# untitledv1_0.net
KiCad netlist of a schematic drawn in EAGLE
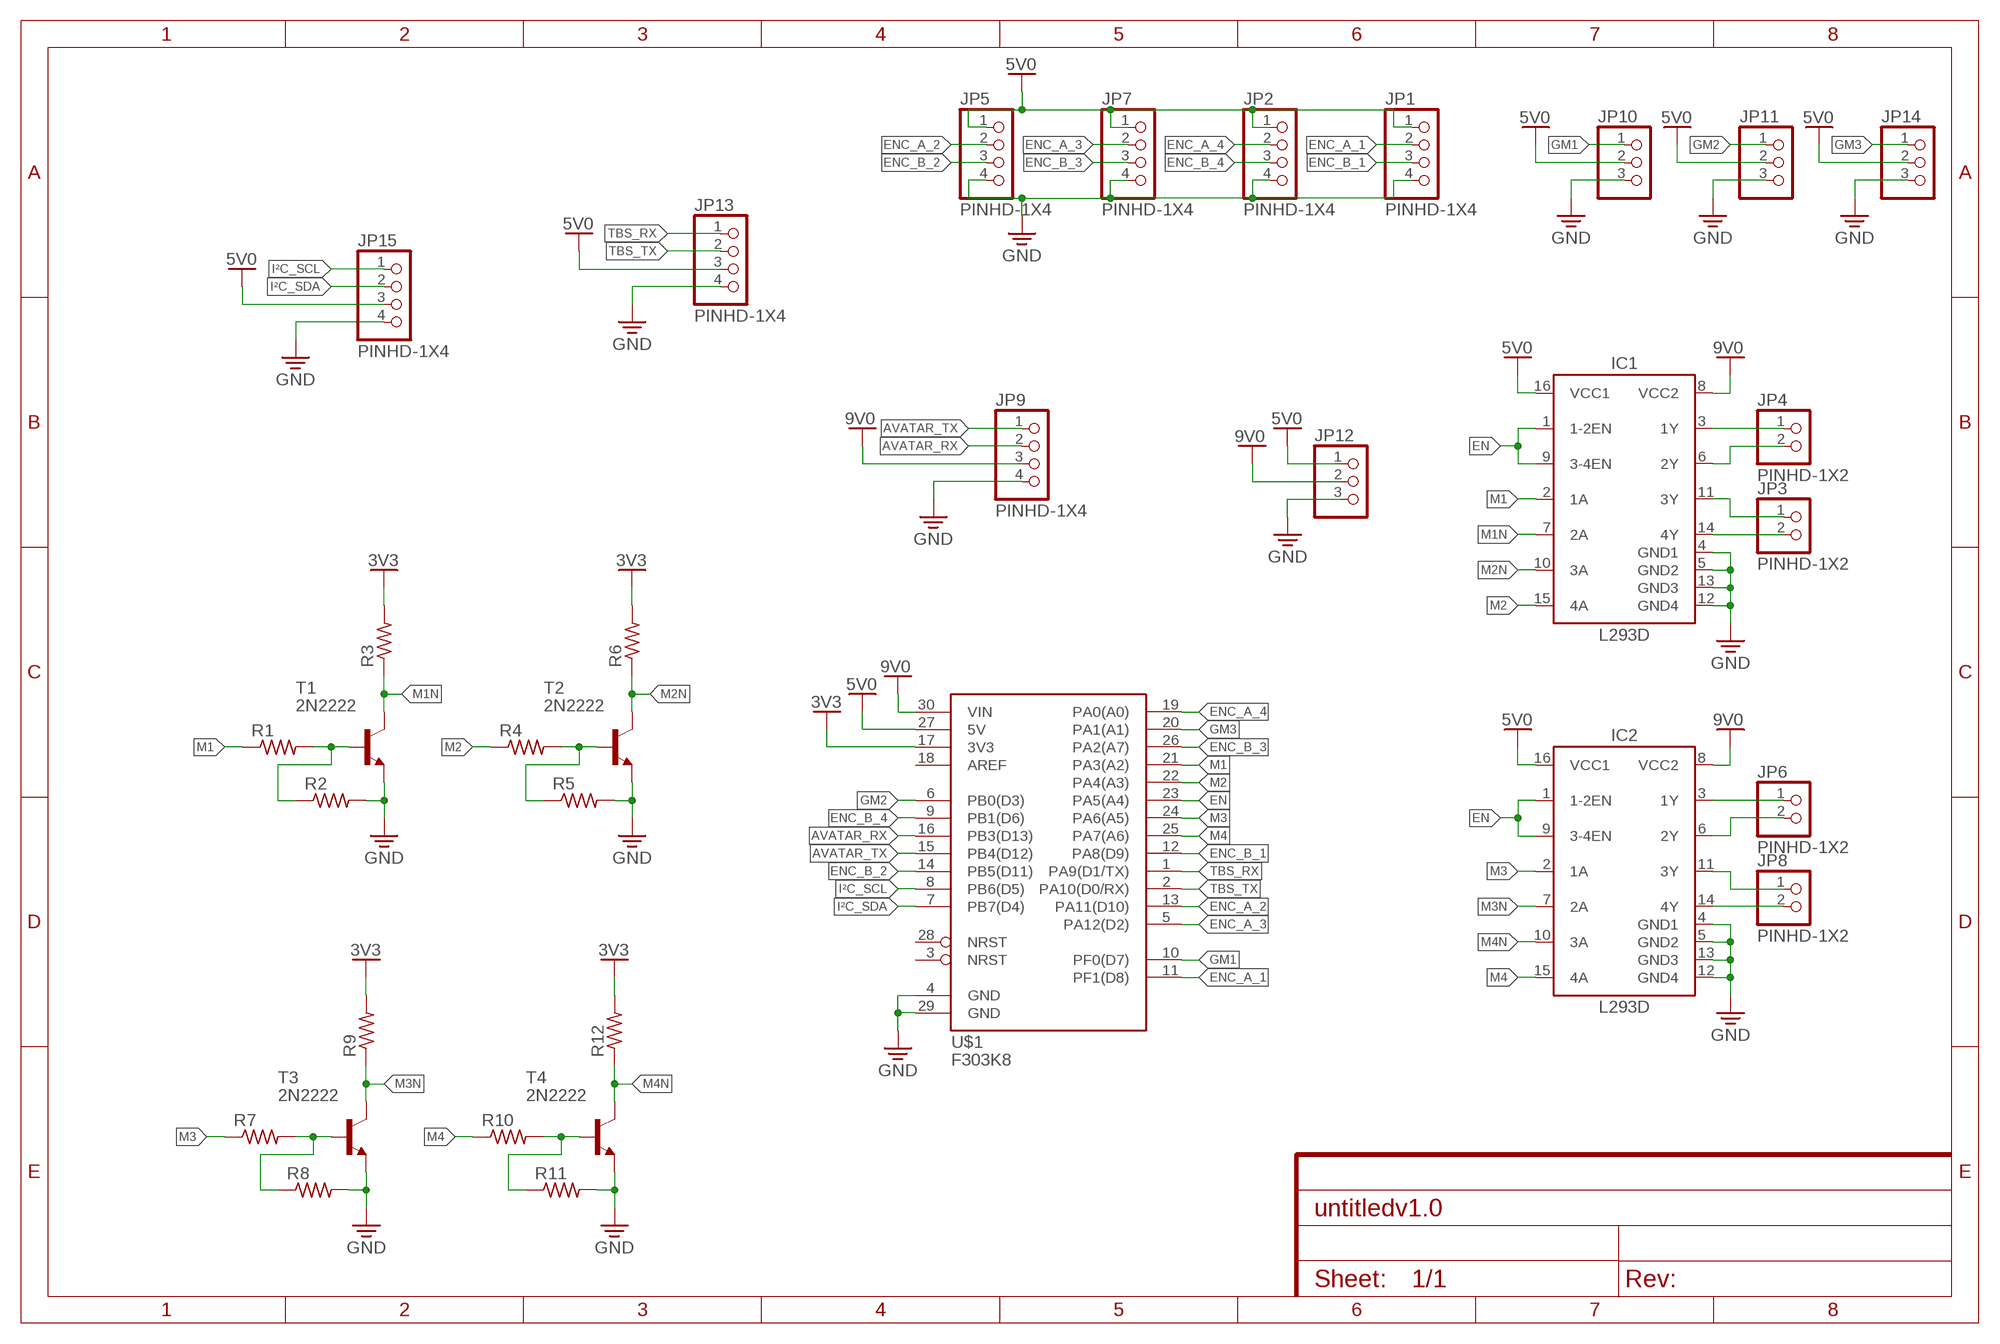
[diagram p0: schematic, sheet 1]

(export (version "E")
  (design (tool "Eeschema 10.0.6"))
  (components
    (comp (ref "IC1")
      (value "L293D")
      (footprint "eagle-import:DIP762W53P254L1969H508Q16B")
      (fields (field (name "MANUFACTURER") "STMicroelectronics"))
      (libsource (lib "eagle-import") (part "L293D"))
    )
    (comp (ref "IC2")
      (value "L293D")
      (footprint "eagle-import:DIP762W53P254L1969H508Q16B")
      (fields (field (name "MANUFACTURER") "STMicroelectronics"))
      (libsource (lib "eagle-import") (part "L293D"))
    )
    (comp (ref "JP1")
      (value "PINHD-1X4")
      (footprint "eagle-import:1X04")
      (libsource (lib "eagle-import") (part "PINHD-1X4"))
    )
    (comp (ref "JP2")
      (value "PINHD-1X4")
      (footprint "eagle-import:1X04")
      (libsource (lib "eagle-import") (part "PINHD-1X4"))
    )
    (comp (ref "JP3")
      (value "PINHD-1X2")
      (footprint "eagle-import:1X02")
      (libsource (lib "eagle-import") (part "PINHD-1X2"))
    )
    (comp (ref "JP4")
      (value "PINHD-1X2")
      (footprint "eagle-import:1X02")
      (libsource (lib "eagle-import") (part "PINHD-1X2"))
    )
    (comp (ref "JP5")
      (value "PINHD-1X4")
      (footprint "eagle-import:1X04")
      (libsource (lib "eagle-import") (part "PINHD-1X4"))
    )
    (comp (ref "JP6")
      (value "PINHD-1X2")
      (footprint "eagle-import:1X02")
      (libsource (lib "eagle-import") (part "PINHD-1X2"))
    )
    (comp (ref "JP7")
      (value "PINHD-1X4")
      (footprint "eagle-import:1X04")
      (libsource (lib "eagle-import") (part "PINHD-1X4"))
    )
    (comp (ref "JP8")
      (value "PINHD-1X2")
      (footprint "eagle-import:1X02")
      (libsource (lib "eagle-import") (part "PINHD-1X2"))
    )
    (comp (ref "JP9")
      (value "PINHD-1X4")
      (footprint "eagle-import:1X04")
      (libsource (lib "eagle-import") (part "PINHD-1X4"))
    )
    (comp (ref "JP10")
      (value "PINHD-1X3")
      (footprint "eagle-import:1X03")
      (libsource (lib "eagle-import") (part "PINHD-1X3"))
    )
    (comp (ref "JP11")
      (value "PINHD-1X3")
      (footprint "eagle-import:1X03")
      (libsource (lib "eagle-import") (part "PINHD-1X3"))
    )
    (comp (ref "JP12")
      (value "PINHD-1X3")
      (footprint "eagle-import:1X03")
      (libsource (lib "eagle-import") (part "PINHD-1X3"))
    )
    (comp (ref "JP13")
      (value "PINHD-1X4")
      (footprint "eagle-import:1X04")
      (libsource (lib "eagle-import") (part "PINHD-1X4"))
    )
    (comp (ref "JP14")
      (value "PINHD-1X3")
      (footprint "eagle-import:1X03")
      (libsource (lib "eagle-import") (part "PINHD-1X3"))
    )
    (comp (ref "JP15")
      (value "PINHD-1X4")
      (footprint "eagle-import:1X04")
      (libsource (lib "eagle-import") (part "PINHD-1X4"))
    )
    (comp (ref "R1")
      (value "R-US_0204/2V")
      (footprint "eagle-import:0204V")
      (libsource (lib "eagle-import") (part "R-US_0204/2V"))
    )
    (comp (ref "R2")
      (value "R-US_0204/2V")
      (footprint "eagle-import:0204V")
      (libsource (lib "eagle-import") (part "R-US_0204/2V"))
    )
    (comp (ref "R3")
      (value "R-US_0204/2V")
      (footprint "eagle-import:0204V")
      (libsource (lib "eagle-import") (part "R-US_0204/2V"))
    )
    (comp (ref "R4")
      (value "R-US_0204/2V")
      (footprint "eagle-import:0204V")
      (libsource (lib "eagle-import") (part "R-US_0204/2V"))
    )
    (comp (ref "R5")
      (value "R-US_0204/2V")
      (footprint "eagle-import:0204V")
      (libsource (lib "eagle-import") (part "R-US_0204/2V"))
    )
    (comp (ref "R6")
      (value "R-US_0204/2V")
      (footprint "eagle-import:0204V")
      (libsource (lib "eagle-import") (part "R-US_0204/2V"))
    )
    (comp (ref "R7")
      (value "R-US_0204/2V")
      (footprint "eagle-import:0204V")
      (libsource (lib "eagle-import") (part "R-US_0204/2V"))
    )
    (comp (ref "R8")
      (value "R-US_0204/2V")
      (footprint "eagle-import:0204V")
      (libsource (lib "eagle-import") (part "R-US_0204/2V"))
    )
    (comp (ref "R9")
      (value "R-US_0204/2V")
      (footprint "eagle-import:0204V")
      (libsource (lib "eagle-import") (part "R-US_0204/2V"))
    )
    (comp (ref "R10")
      (value "R-US_0204/2V")
      (footprint "eagle-import:0204V")
      (libsource (lib "eagle-import") (part "R-US_0204/2V"))
    )
    (comp (ref "R11")
      (value "R-US_0204/2V")
      (footprint "eagle-import:0204V")
      (libsource (lib "eagle-import") (part "R-US_0204/2V"))
    )
    (comp (ref "R12")
      (value "R-US_0204/2V")
      (footprint "eagle-import:0204V")
      (libsource (lib "eagle-import") (part "R-US_0204/2V"))
    )
    (comp (ref "T1")
      (value "2N2222")
      (footprint "eagle-import:TO92-EBC-OVAL")
      (libsource (lib "eagle-import") (part "2N2222"))
    )
    (comp (ref "T2")
      (value "2N2222")
      (footprint "eagle-import:TO92-EBC-OVAL")
      (libsource (lib "eagle-import") (part "2N2222"))
    )
    (comp (ref "T3")
      (value "2N2222")
      (footprint "eagle-import:TO92-EBC-OVAL")
      (libsource (lib "eagle-import") (part "2N2222"))
    )
    (comp (ref "T4")
      (value "2N2222")
      (footprint "eagle-import:TO92-EBC-OVAL")
      (libsource (lib "eagle-import") (part "2N2222"))
    )
    (comp (ref "U$1")
      (value "F303K8")
      (footprint "eagle-import:NUCLEO_F303K8-V2")
      (libsource (lib "eagle-import") (part "F303K8"))
    )
  )
  (nets
    (net (code "1") (name "3V3") (class "Default")
      (node (ref "R12") (pin "2") (pinfunction "2_2") (pintype "passive"))
      (node (ref "R3") (pin "2") (pinfunction "2_2") (pintype "passive"))
      (node (ref "R6") (pin "2") (pinfunction "2_2") (pintype "passive"))
      (node (ref "R9") (pin "2") (pinfunction "2_2") (pintype "passive"))
      (node (ref "U$1") (pin "17") (pinfunction "3V3_17") (pintype "output"))
    )
    (net (code "2") (name "5V0") (class "Default")
      (node (ref "IC1") (pin "16") (pinfunction "VCC1_16") (pintype "passive"))
      (node (ref "IC2") (pin "16") (pinfunction "VCC1_16") (pintype "passive"))
      (node (ref "JP1") (pin "1") (pinfunction "1_1") (pintype "passive"))
      (node (ref "JP10") (pin "2") (pinfunction "2_2") (pintype "passive"))
      (node (ref "JP11") (pin "2") (pinfunction "2_2") (pintype "passive"))
      (node (ref "JP12") (pin "1") (pinfunction "1_1") (pintype "passive"))
      (node (ref "JP13") (pin "3") (pinfunction "3_3") (pintype "passive"))
      (node (ref "JP14") (pin "2") (pinfunction "2_2") (pintype "passive"))
      (node (ref "JP15") (pin "3") (pinfunction "3_3") (pintype "passive"))
      (node (ref "JP2") (pin "1") (pinfunction "1_1") (pintype "passive"))
      (node (ref "JP5") (pin "1") (pinfunction "1_1") (pintype "passive"))
      (node (ref "JP7") (pin "1") (pinfunction "1_1") (pintype "passive"))
      (node (ref "U$1") (pin "27") (pinfunction "5V_27") (pintype "power_in"))
    )
    (net (code "3") (name "9V0") (class "Default")
      (node (ref "IC1") (pin "8") (pinfunction "VCC2_8") (pintype "passive"))
      (node (ref "IC2") (pin "8") (pinfunction "VCC2_8") (pintype "passive"))
      (node (ref "JP12") (pin "2") (pinfunction "2_2") (pintype "passive"))
      (node (ref "JP9") (pin "3") (pinfunction "3_3") (pintype "passive"))
      (node (ref "U$1") (pin "30") (pinfunction "VIN_30") (pintype "power_in"))
    )
    (net (code "4") (name "AVATAR_RX") (class "Default")
      (node (ref "JP9") (pin "2") (pinfunction "2_2") (pintype "passive"))
      (node (ref "U$1") (pin "16") (pinfunction "PB3(D13)_16") (pintype "bidirectional"))
    )
    (net (code "5") (name "AVATAR_TX") (class "Default")
      (node (ref "JP9") (pin "1") (pinfunction "1_1") (pintype "passive"))
      (node (ref "U$1") (pin "15") (pinfunction "PB4(D12)_15") (pintype "bidirectional"))
    )
    (net (code "6") (name "EN") (class "Default")
      (node (ref "IC1") (pin "1") (pinfunction "1-2EN_1") (pintype "input"))
      (node (ref "IC1") (pin "9") (pinfunction "3-4EN_9") (pintype "input"))
      (node (ref "IC2") (pin "1") (pinfunction "1-2EN_1") (pintype "input"))
      (node (ref "IC2") (pin "9") (pinfunction "3-4EN_9") (pintype "input"))
      (node (ref "U$1") (pin "23") (pinfunction "PA5(A4)_23") (pintype "bidirectional"))
    )
    (net (code "7") (name "ENC_A_1") (class "Default")
      (node (ref "JP1") (pin "2") (pinfunction "2_2") (pintype "passive"))
      (node (ref "U$1") (pin "11") (pinfunction "PF1(D8)_11") (pintype "bidirectional"))
    )
    (net (code "8") (name "ENC_A_2") (class "Default")
      (node (ref "JP5") (pin "2") (pinfunction "2_2") (pintype "passive"))
      (node (ref "U$1") (pin "13") (pinfunction "PA11(D10)_13") (pintype "bidirectional"))
    )
    (net (code "9") (name "ENC_A_3") (class "Default")
      (node (ref "JP7") (pin "2") (pinfunction "2_2") (pintype "passive"))
      (node (ref "U$1") (pin "5") (pinfunction "PA12(D2)_5") (pintype "bidirectional"))
    )
    (net (code "10") (name "ENC_A_4") (class "Default")
      (node (ref "JP2") (pin "2") (pinfunction "2_2") (pintype "passive"))
      (node (ref "U$1") (pin "19") (pinfunction "PA0(A0)_19") (pintype "bidirectional"))
    )
    (net (code "11") (name "ENC_B_1") (class "Default")
      (node (ref "JP1") (pin "3") (pinfunction "3_3") (pintype "passive"))
      (node (ref "U$1") (pin "12") (pinfunction "PA8(D9)_12") (pintype "bidirectional"))
    )
    (net (code "12") (name "ENC_B_2") (class "Default")
      (node (ref "JP5") (pin "3") (pinfunction "3_3") (pintype "passive"))
      (node (ref "U$1") (pin "14") (pinfunction "PB5(D11)_14") (pintype "bidirectional"))
    )
    (net (code "13") (name "ENC_B_3") (class "Default")
      (node (ref "JP7") (pin "3") (pinfunction "3_3") (pintype "passive"))
      (node (ref "U$1") (pin "26") (pinfunction "PA2(A7)_26") (pintype "bidirectional"))
    )
    (net (code "14") (name "ENC_B_4") (class "Default")
      (node (ref "JP2") (pin "3") (pinfunction "3_3") (pintype "passive"))
      (node (ref "U$1") (pin "9") (pinfunction "PB1(D6)_9") (pintype "bidirectional"))
    )
    (net (code "15") (name "GM1") (class "Default")
      (node (ref "JP10") (pin "1") (pinfunction "1_1") (pintype "passive"))
      (node (ref "U$1") (pin "10") (pinfunction "PF0(D7)_10") (pintype "bidirectional"))
    )
    (net (code "16") (name "GM2") (class "Default")
      (node (ref "JP11") (pin "1") (pinfunction "1_1") (pintype "passive"))
      (node (ref "U$1") (pin "6") (pinfunction "PB0(D3)_6") (pintype "bidirectional"))
    )
    (net (code "17") (name "GM3") (class "Default")
      (node (ref "JP14") (pin "1") (pinfunction "1_1") (pintype "passive"))
      (node (ref "U$1") (pin "20") (pinfunction "PA1(A1)_20") (pintype "bidirectional"))
    )
    (net (code "18") (name "GND") (class "Default")
      (node (ref "IC1") (pin "12") (pinfunction "GND4_12") (pintype "passive"))
      (node (ref "IC1") (pin "13") (pinfunction "GND3_13") (pintype "passive"))
      (node (ref "IC1") (pin "4") (pinfunction "GND1_4") (pintype "passive"))
      (node (ref "IC1") (pin "5") (pinfunction "GND2_5") (pintype "passive"))
      (node (ref "IC2") (pin "12") (pinfunction "GND4_12") (pintype "passive"))
      (node (ref "IC2") (pin "13") (pinfunction "GND3_13") (pintype "passive"))
      (node (ref "IC2") (pin "4") (pinfunction "GND1_4") (pintype "passive"))
      (node (ref "IC2") (pin "5") (pinfunction "GND2_5") (pintype "passive"))
      (node (ref "JP1") (pin "4") (pinfunction "4_4") (pintype "passive"))
      (node (ref "JP10") (pin "3") (pinfunction "3_3") (pintype "passive"))
      (node (ref "JP11") (pin "3") (pinfunction "3_3") (pintype "passive"))
      (node (ref "JP12") (pin "3") (pinfunction "3_3") (pintype "passive"))
      (node (ref "JP13") (pin "4") (pinfunction "4_4") (pintype "passive"))
      (node (ref "JP14") (pin "3") (pinfunction "3_3") (pintype "passive"))
      (node (ref "JP15") (pin "4") (pinfunction "4_4") (pintype "passive"))
      (node (ref "JP2") (pin "4") (pinfunction "4_4") (pintype "passive"))
      (node (ref "JP5") (pin "4") (pinfunction "4_4") (pintype "passive"))
      (node (ref "JP7") (pin "4") (pinfunction "4_4") (pintype "passive"))
      (node (ref "JP9") (pin "4") (pinfunction "4_4") (pintype "passive"))
      (node (ref "R11") (pin "2") (pinfunction "2_2") (pintype "passive"))
      (node (ref "R2") (pin "2") (pinfunction "2_2") (pintype "passive"))
      (node (ref "R5") (pin "2") (pinfunction "2_2") (pintype "passive"))
      (node (ref "R8") (pin "2") (pinfunction "2_2") (pintype "passive"))
      (node (ref "T1") (pin "E") (pinfunction "E_E") (pintype "passive"))
      (node (ref "T2") (pin "E") (pinfunction "E_E") (pintype "passive"))
      (node (ref "T3") (pin "E") (pinfunction "E_E") (pintype "passive"))
      (node (ref "T4") (pin "E") (pinfunction "E_E") (pintype "passive"))
      (node (ref "U$1") (pin "29") (pinfunction "GND_29") (pintype "power_in"))
      (node (ref "U$1") (pin "4") (pinfunction "GND_4") (pintype "power_in"))
    )
    (net (code "19") (name "I²C_SCL") (class "Default")
      (node (ref "JP15") (pin "1") (pinfunction "1_1") (pintype "passive"))
      (node (ref "U$1") (pin "8") (pinfunction "PB6(D5)_8") (pintype "bidirectional"))
    )
    (net (code "20") (name "I²C_SDA") (class "Default")
      (node (ref "JP15") (pin "2") (pinfunction "2_2") (pintype "passive"))
      (node (ref "U$1") (pin "7") (pinfunction "PB7(D4)_7") (pintype "bidirectional"))
    )
    (net (code "21") (name "M1") (class "Default")
      (node (ref "IC1") (pin "2") (pinfunction "1A_2") (pintype "input"))
      (node (ref "R1") (pin "1") (pinfunction "1_1") (pintype "passive"))
      (node (ref "U$1") (pin "21") (pinfunction "PA3(A2)_21") (pintype "bidirectional"))
    )
    (net (code "22") (name "M1N") (class "Default")
      (node (ref "IC1") (pin "7") (pinfunction "2A_7") (pintype "input"))
      (node (ref "R3") (pin "1") (pinfunction "1_1") (pintype "passive"))
      (node (ref "T1") (pin "C") (pinfunction "C_C") (pintype "passive"))
    )
    (net (code "23") (name "M2") (class "Default")
      (node (ref "IC1") (pin "15") (pinfunction "4A_15") (pintype "input"))
      (node (ref "R4") (pin "1") (pinfunction "1_1") (pintype "passive"))
      (node (ref "U$1") (pin "22") (pinfunction "PA4(A3)_22") (pintype "bidirectional"))
    )
    (net (code "24") (name "M2N") (class "Default")
      (node (ref "IC1") (pin "10") (pinfunction "3A_10") (pintype "input"))
      (node (ref "R6") (pin "1") (pinfunction "1_1") (pintype "passive"))
      (node (ref "T2") (pin "C") (pinfunction "C_C") (pintype "passive"))
    )
    (net (code "25") (name "M3") (class "Default")
      (node (ref "IC2") (pin "2") (pinfunction "1A_2") (pintype "input"))
      (node (ref "R7") (pin "1") (pinfunction "1_1") (pintype "passive"))
      (node (ref "U$1") (pin "24") (pinfunction "PA6(A5)_24") (pintype "bidirectional"))
    )
    (net (code "26") (name "M3N") (class "Default")
      (node (ref "IC2") (pin "7") (pinfunction "2A_7") (pintype "input"))
      (node (ref "R9") (pin "1") (pinfunction "1_1") (pintype "passive"))
      (node (ref "T3") (pin "C") (pinfunction "C_C") (pintype "passive"))
    )
    (net (code "27") (name "M4") (class "Default")
      (node (ref "IC2") (pin "15") (pinfunction "4A_15") (pintype "input"))
      (node (ref "R10") (pin "1") (pinfunction "1_1") (pintype "passive"))
      (node (ref "U$1") (pin "25") (pinfunction "PA7(A6)_25") (pintype "bidirectional"))
    )
    (net (code "28") (name "M4N") (class "Default")
      (node (ref "IC2") (pin "10") (pinfunction "3A_10") (pintype "input"))
      (node (ref "R12") (pin "1") (pinfunction "1_1") (pintype "passive"))
      (node (ref "T4") (pin "C") (pinfunction "C_C") (pintype "passive"))
    )
    (net (code "29") (name "Net-(IC1-1Y)") (class "Default")
      (node (ref "IC1") (pin "3") (pinfunction "1Y_3") (pintype "output"))
      (node (ref "JP4") (pin "1") (pinfunction "1_1") (pintype "passive"))
    )
    (net (code "30") (name "Net-(IC1-2Y)") (class "Default")
      (node (ref "IC1") (pin "6") (pinfunction "2Y_6") (pintype "output"))
      (node (ref "JP4") (pin "2") (pinfunction "2_2") (pintype "passive"))
    )
    (net (code "31") (name "Net-(IC1-3Y)") (class "Default")
      (node (ref "IC1") (pin "11") (pinfunction "3Y_11") (pintype "output"))
      (node (ref "JP3") (pin "1") (pinfunction "1_1") (pintype "passive"))
    )
    (net (code "32") (name "Net-(IC1-4Y)") (class "Default")
      (node (ref "IC1") (pin "14") (pinfunction "4Y_14") (pintype "output"))
      (node (ref "JP3") (pin "2") (pinfunction "2_2") (pintype "passive"))
    )
    (net (code "33") (name "Net-(IC2-1Y)") (class "Default")
      (node (ref "IC2") (pin "3") (pinfunction "1Y_3") (pintype "output"))
      (node (ref "JP6") (pin "1") (pinfunction "1_1") (pintype "passive"))
    )
    (net (code "34") (name "Net-(IC2-2Y)") (class "Default")
      (node (ref "IC2") (pin "6") (pinfunction "2Y_6") (pintype "output"))
      (node (ref "JP6") (pin "2") (pinfunction "2_2") (pintype "passive"))
    )
    (net (code "35") (name "Net-(IC2-3Y)") (class "Default")
      (node (ref "IC2") (pin "11") (pinfunction "3Y_11") (pintype "output"))
      (node (ref "JP8") (pin "1") (pinfunction "1_1") (pintype "passive"))
    )
    (net (code "36") (name "Net-(IC2-4Y)") (class "Default")
      (node (ref "IC2") (pin "14") (pinfunction "4Y_14") (pintype "output"))
      (node (ref "JP8") (pin "2") (pinfunction "2_2") (pintype "passive"))
    )
    (net (code "37") (name "Net-(R1-Pad2)") (class "Default")
      (node (ref "R1") (pin "2") (pinfunction "2_2") (pintype "passive"))
      (node (ref "R2") (pin "1") (pinfunction "1_1") (pintype "passive"))
      (node (ref "T1") (pin "B") (pinfunction "B_B") (pintype "passive"))
    )
    (net (code "38") (name "Net-(R4-Pad2)") (class "Default")
      (node (ref "R4") (pin "2") (pinfunction "2_2") (pintype "passive"))
      (node (ref "R5") (pin "1") (pinfunction "1_1") (pintype "passive"))
      (node (ref "T2") (pin "B") (pinfunction "B_B") (pintype "passive"))
    )
    (net (code "39") (name "Net-(R7-Pad2)") (class "Default")
      (node (ref "R7") (pin "2") (pinfunction "2_2") (pintype "passive"))
      (node (ref "R8") (pin "1") (pinfunction "1_1") (pintype "passive"))
      (node (ref "T3") (pin "B") (pinfunction "B_B") (pintype "passive"))
    )
    (net (code "40") (name "Net-(R10-Pad2)") (class "Default")
      (node (ref "R10") (pin "2") (pinfunction "2_2") (pintype "passive"))
      (node (ref "R11") (pin "1") (pinfunction "1_1") (pintype "passive"))
      (node (ref "T4") (pin "B") (pinfunction "B_B") (pintype "passive"))
    )
    (net (code "41") (name "TBS_RX") (class "Default")
      (node (ref "JP13") (pin "1") (pinfunction "1_1") (pintype "passive"))
      (node (ref "U$1") (pin "1") (pinfunction "PA9(D1/TX)_1") (pintype "bidirectional"))
    )
    (net (code "42") (name "TBS_TX") (class "Default")
      (node (ref "JP13") (pin "2") (pinfunction "2_2") (pintype "passive"))
      (node (ref "U$1") (pin "2") (pinfunction "PA10(D0/RX)_2") (pintype "bidirectional"))
    )
    (net (code "43") (name "unconnected-(U$1-AREF-Pad18)") (class "Default")
      (node (ref "U$1") (pin "18") (pinfunction "AREF_18") (pintype "input"))
    )
    (net (code "44") (name "unconnected-(U$1-NRST-Pad3)") (class "Default")
      (node (ref "U$1") (pin "3") (pinfunction "NRST_3") (pintype "input"))
    )
    (net (code "45") (name "unconnected-(U$1-NRST-Pad28)") (class "Default")
      (node (ref "U$1") (pin "28") (pinfunction "NRST_28") (pintype "input"))
    )
  )
)
